# Low_Pass_Gate.net
KiCad netlist of a schematic drawn in EAGLE
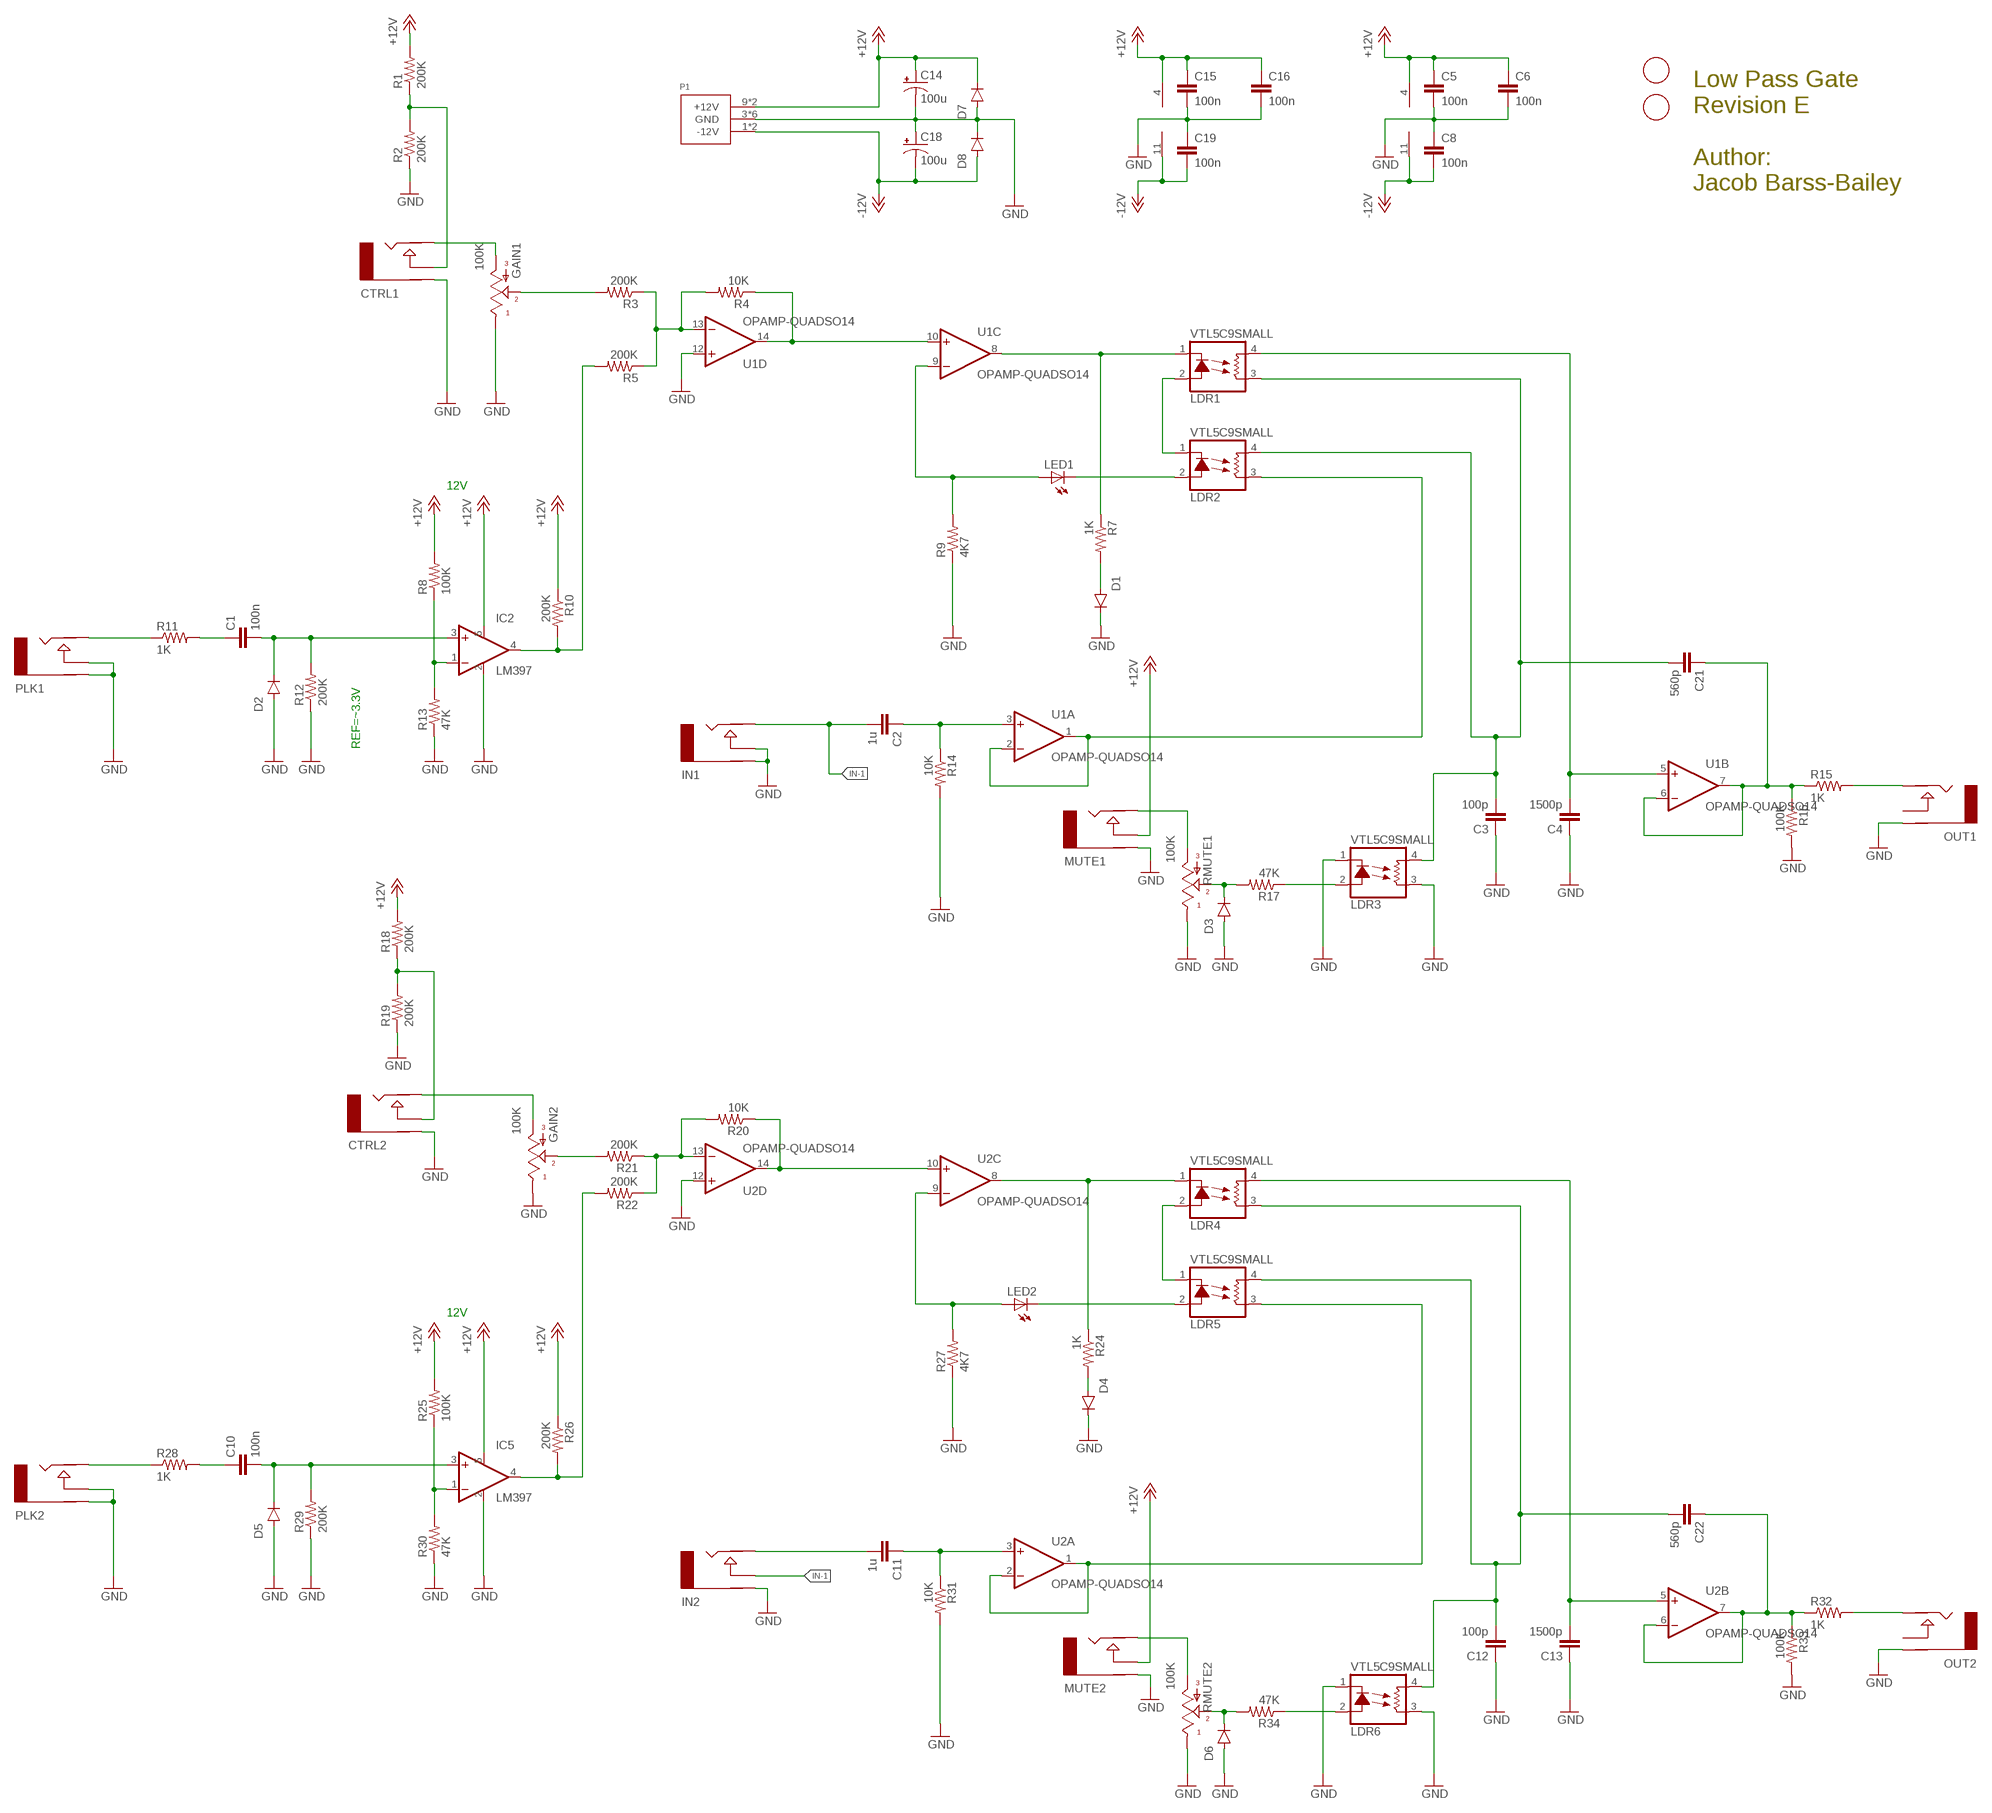
[diagram p0: schematic, sheet 1]

(export (version "E")
  (design (tool "Eeschema 10.0.6"))
  (components
    (comp (ref "C1")
      (value "100n")
      (footprint "eagle-import:0805")
      (libsource (lib "eagle-import") (part "CAP0805"))
    )
    (comp (ref "C2")
      (value "1u")
      (footprint "eagle-import:0805")
      (libsource (lib "eagle-import") (part "CAP0805"))
    )
    (comp (ref "C3")
      (value "100p")
      (footprint "eagle-import:0805")
      (libsource (lib "eagle-import") (part "CAP0805"))
    )
    (comp (ref "C4")
      (value "1500p")
      (footprint "eagle-import:0805")
      (libsource (lib "eagle-import") (part "CAP0805"))
    )
    (comp (ref "C5")
      (value "100n")
      (footprint "eagle-import:0805")
      (libsource (lib "eagle-import") (part "CAP0805"))
    )
    (comp (ref "C6")
      (value "100n")
      (footprint "eagle-import:0805")
      (libsource (lib "eagle-import") (part "CAP0805"))
    )
    (comp (ref "C8")
      (value "100n")
      (footprint "eagle-import:0805")
      (libsource (lib "eagle-import") (part "CAP0805"))
    )
    (comp (ref "C10")
      (value "100n")
      (footprint "eagle-import:0805")
      (libsource (lib "eagle-import") (part "CAP0805"))
    )
    (comp (ref "C11")
      (value "1u")
      (footprint "eagle-import:0805")
      (libsource (lib "eagle-import") (part "CAP0805"))
    )
    (comp (ref "C12")
      (value "100p")
      (footprint "eagle-import:0805")
      (libsource (lib "eagle-import") (part "CAP0805"))
    )
    (comp (ref "C13")
      (value "1500p")
      (footprint "eagle-import:0805")
      (libsource (lib "eagle-import") (part "CAP0805"))
    )
    (comp (ref "C14")
      (value "100u")
      (footprint "eagle-import:PANASONIC_D")
      (libsource (lib "eagle-import") (part "CAP_POLD"))
    )
    (comp (ref "C15")
      (value "100n")
      (footprint "eagle-import:0805")
      (libsource (lib "eagle-import") (part "CAP0805"))
    )
    (comp (ref "C16")
      (value "100n")
      (footprint "eagle-import:0805")
      (libsource (lib "eagle-import") (part "CAP0805"))
    )
    (comp (ref "C18")
      (value "100u")
      (footprint "eagle-import:PANASONIC_D")
      (libsource (lib "eagle-import") (part "CAP_POLD"))
    )
    (comp (ref "C19")
      (value "100n")
      (footprint "eagle-import:0805")
      (libsource (lib "eagle-import") (part "CAP0805"))
    )
    (comp (ref "C21")
      (value "560p")
      (footprint "eagle-import:0805")
      (libsource (lib "eagle-import") (part "CAP0805"))
    )
    (comp (ref "C22")
      (value "560p")
      (footprint "eagle-import:0805")
      (libsource (lib "eagle-import") (part "CAP0805"))
    )
    (comp (ref "CTRL1")
      (value "AUDIO-JACKINLINE-FLOATGND")
      (footprint "eagle-import:ERTHENVAR-JACK-INLINE-SHAREGND550")
      (libsource (lib "eagle-import") (part "AUDIO-JACKINLINE-FLOATGND"))
    )
    (comp (ref "CTRL2")
      (value "AUDIO-JACKINLINE-FLOATGND")
      (footprint "eagle-import:ERTHENVAR-JACK-INLINE-SHAREGND550")
      (libsource (lib "eagle-import") (part "AUDIO-JACKINLINE-FLOATGND"))
    )
    (comp (ref "D1")
      (value "DIODE-SOD323-W")
      (footprint "eagle-import:SOD323-W")
      (libsource (lib "eagle-import") (part "DIODE-SOD323-W"))
    )
    (comp (ref "D2")
      (value "DIODE-SOD323-W")
      (footprint "eagle-import:SOD323-W")
      (libsource (lib "eagle-import") (part "DIODE-SOD323-W"))
    )
    (comp (ref "D3")
      (value "DIODE-SOD323-W")
      (footprint "eagle-import:SOD323-W")
      (libsource (lib "eagle-import") (part "DIODE-SOD323-W"))
    )
    (comp (ref "D4")
      (value "DIODE-SOD323-W")
      (footprint "eagle-import:SOD323-W")
      (libsource (lib "eagle-import") (part "DIODE-SOD323-W"))
    )
    (comp (ref "D5")
      (value "DIODE-SOD323-W")
      (footprint "eagle-import:SOD323-W")
      (libsource (lib "eagle-import") (part "DIODE-SOD323-W"))
    )
    (comp (ref "D6")
      (value "DIODE-SOD323-W")
      (footprint "eagle-import:SOD323-W")
      (libsource (lib "eagle-import") (part "DIODE-SOD323-W"))
    )
    (comp (ref "D7")
      (value "DIODE-SOD323-W")
      (footprint "eagle-import:SOD323-W")
      (libsource (lib "eagle-import") (part "DIODE-SOD323-W"))
    )
    (comp (ref "D8")
      (value "DIODE-SOD323-W")
      (footprint "eagle-import:SOD323-W")
      (libsource (lib "eagle-import") (part "DIODE-SOD323-W"))
    )
    (comp (ref "GAIN1")
      (value "100K")
      (footprint "eagle-import:ALPS_POT_KIT")
      (libsource (lib "eagle-import") (part "POTALPS-KIT"))
    )
    (comp (ref "GAIN2")
      (value "100K")
      (footprint "eagle-import:ALPS_POT_KIT")
      (libsource (lib "eagle-import") (part "POTALPS-KIT"))
    )
    (comp (ref "IC2")
      (value "LM397")
      (footprint "eagle-import:SOT23-5")
      (libsource (lib "eagle-import") (part "LM397"))
    )
    (comp (ref "IC5")
      (value "LM397")
      (footprint "eagle-import:SOT23-5")
      (libsource (lib "eagle-import") (part "LM397"))
    )
    (comp (ref "IN1")
      (value "AUDIO-JACKINLINE-FLOATGND")
      (footprint "eagle-import:ERTHENVAR-JACK-INLINE-SHAREGND550")
      (libsource (lib "eagle-import") (part "AUDIO-JACKINLINE-FLOATGND"))
    )
    (comp (ref "IN2")
      (value "AUDIO-JACKINLINE-FLOATGND")
      (footprint "eagle-import:ERTHENVAR-JACK-INLINE-SHAREGND550")
      (libsource (lib "eagle-import") (part "AUDIO-JACKINLINE-FLOATGND"))
    )
    (comp (ref "LDR1")
      (value "VTL5C9SMALL")
      (footprint "eagle-import:VTL5C-SMALL")
      (fields (field (name "MF") "VACTEC PHOTO") (field (name "MPN") "VTL5C9"))
      (libsource (lib "eagle-import") (part "VTL5CSMALL9"))
    )
    (comp (ref "LDR2")
      (value "VTL5C9SMALL")
      (footprint "eagle-import:VTL5C-SMALL")
      (fields (field (name "MF") "VACTEC PHOTO") (field (name "MPN") "VTL5C9"))
      (libsource (lib "eagle-import") (part "VTL5CSMALL9"))
    )
    (comp (ref "LDR3")
      (value "VTL5C9SMALL")
      (footprint "eagle-import:VTL5C-SMALL")
      (fields (field (name "MF") "VACTEC PHOTO") (field (name "MPN") "VTL5C9"))
      (libsource (lib "eagle-import") (part "VTL5CSMALL9"))
    )
    (comp (ref "LDR4")
      (value "VTL5C9SMALL")
      (footprint "eagle-import:VTL5C-SMALL")
      (fields (field (name "MF") "VACTEC PHOTO") (field (name "MPN") "VTL5C9"))
      (libsource (lib "eagle-import") (part "VTL5CSMALL9"))
    )
    (comp (ref "LDR5")
      (value "VTL5C9SMALL")
      (footprint "eagle-import:VTL5C-SMALL")
      (fields (field (name "MF") "VACTEC PHOTO") (field (name "MPN") "VTL5C9"))
      (libsource (lib "eagle-import") (part "VTL5CSMALL9"))
    )
    (comp (ref "LDR6")
      (value "VTL5C9SMALL")
      (footprint "eagle-import:VTL5C-SMALL")
      (fields (field (name "MF") "VACTEC PHOTO") (field (name "MPN") "VTL5C9"))
      (libsource (lib "eagle-import") (part "VTL5CSMALL9"))
    )
    (comp (ref "LED1")
      (value "LED3MM")
      (footprint "eagle-import:LED3MM")
      (libsource (lib "eagle-import") (part "LED3MM"))
    )
    (comp (ref "LED2")
      (value "LED3MM")
      (footprint "eagle-import:LED3MM")
      (libsource (lib "eagle-import") (part "LED3MM"))
    )
    (comp (ref "MUTE1")
      (value "AUDIO-JACKINLINE")
      (footprint "eagle-import:ERTHENVAR-JACK-INLINE")
      (libsource (lib "eagle-import") (part "AUDIO-JACKINLINE"))
    )
    (comp (ref "MUTE2")
      (value "AUDIO-JACKINLINE")
      (footprint "eagle-import:ERTHENVAR-JACK-INLINE")
      (libsource (lib "eagle-import") (part "AUDIO-JACKINLINE"))
    )
    (comp (ref "OUT1")
      (value "AUDIO-JACKINLINE")
      (footprint "eagle-import:ERTHENVAR-JACK-INLINE")
      (libsource (lib "eagle-import") (part "AUDIO-JACKINLINE"))
    )
    (comp (ref "OUT2")
      (value "AUDIO-JACKINLINE")
      (footprint "eagle-import:ERTHENVAR-JACK-INLINE")
      (libsource (lib "eagle-import") (part "AUDIO-JACKINLINE"))
    )
    (comp (ref "P1")
      (value "POWER_SIMPLE10_SHROUDED")
      (footprint "eagle-import:POWER_10_SHROUDED")
      (libsource (lib "eagle-import") (part "POWER_SIMPLE10_SHROUDED"))
    )
    (comp (ref "PLK1")
      (value "AUDIO-JACKINLINE")
      (footprint "eagle-import:ERTHENVAR-JACK-INLINE")
      (libsource (lib "eagle-import") (part "AUDIO-JACKINLINE"))
    )
    (comp (ref "PLK2")
      (value "AUDIO-JACKINLINE")
      (footprint "eagle-import:ERTHENVAR-JACK-INLINE")
      (libsource (lib "eagle-import") (part "AUDIO-JACKINLINE"))
    )
    (comp (ref "R1")
      (value "200K")
      (footprint "eagle-import:0603-RES")
      (libsource (lib "eagle-import") (part "RESISTOR0603-RES"))
    )
    (comp (ref "R2")
      (value "200K")
      (footprint "eagle-import:0603-RES")
      (libsource (lib "eagle-import") (part "RESISTOR0603-RES"))
    )
    (comp (ref "R3")
      (value "200K")
      (footprint "eagle-import:0603-RES")
      (libsource (lib "eagle-import") (part "RESISTOR0603-RES"))
    )
    (comp (ref "R4")
      (value "10K")
      (footprint "eagle-import:0603-RES")
      (libsource (lib "eagle-import") (part "RESISTOR0603-RES"))
    )
    (comp (ref "R5")
      (value "200K")
      (footprint "eagle-import:0603-RES")
      (libsource (lib "eagle-import") (part "RESISTOR0603-RES"))
    )
    (comp (ref "R7")
      (value "1K")
      (footprint "eagle-import:0603-RES")
      (libsource (lib "eagle-import") (part "RESISTOR0603-RES"))
    )
    (comp (ref "R8")
      (value "100K")
      (footprint "eagle-import:0603-RES")
      (libsource (lib "eagle-import") (part "RESISTOR0603-RES"))
    )
    (comp (ref "R9")
      (value "4K7")
      (footprint "eagle-import:0603-RES")
      (libsource (lib "eagle-import") (part "RESISTOR0603-RES"))
    )
    (comp (ref "R10")
      (value "200K")
      (footprint "eagle-import:0603-RES")
      (libsource (lib "eagle-import") (part "RESISTOR0603-RES"))
    )
    (comp (ref "R11")
      (value "1K")
      (footprint "eagle-import:0603-RES")
      (libsource (lib "eagle-import") (part "RESISTOR0603-RES"))
    )
    (comp (ref "R12")
      (value "200K")
      (footprint "eagle-import:0603-RES")
      (libsource (lib "eagle-import") (part "RESISTOR0603-RES"))
    )
    (comp (ref "R13")
      (value "47K")
      (footprint "eagle-import:0603-RES")
      (libsource (lib "eagle-import") (part "RESISTOR0603-RES"))
    )
    (comp (ref "R14")
      (value "10K")
      (footprint "eagle-import:0603-RES")
      (libsource (lib "eagle-import") (part "RESISTOR0603-RES"))
    )
    (comp (ref "R15")
      (value "1K")
      (footprint "eagle-import:0603-RES")
      (libsource (lib "eagle-import") (part "RESISTOR0603-RES"))
    )
    (comp (ref "R16")
      (value "100K")
      (footprint "eagle-import:0603-RES")
      (libsource (lib "eagle-import") (part "RESISTOR0603-RES"))
    )
    (comp (ref "R17")
      (value "47K")
      (footprint "eagle-import:0603-RES")
      (libsource (lib "eagle-import") (part "RESISTOR0603-RES"))
    )
    (comp (ref "R18")
      (value "200K")
      (footprint "eagle-import:0603-RES")
      (libsource (lib "eagle-import") (part "RESISTOR0603-RES"))
    )
    (comp (ref "R19")
      (value "200K")
      (footprint "eagle-import:0603-RES")
      (libsource (lib "eagle-import") (part "RESISTOR0603-RES"))
    )
    (comp (ref "R20")
      (value "10K")
      (footprint "eagle-import:0603-RES")
      (libsource (lib "eagle-import") (part "RESISTOR0603-RES"))
    )
    (comp (ref "R21")
      (value "200K")
      (footprint "eagle-import:0603-RES")
      (libsource (lib "eagle-import") (part "RESISTOR0603-RES"))
    )
    (comp (ref "R22")
      (value "200K")
      (footprint "eagle-import:0603-RES")
      (libsource (lib "eagle-import") (part "RESISTOR0603-RES"))
    )
    (comp (ref "R24")
      (value "1K")
      (footprint "eagle-import:0603-RES")
      (libsource (lib "eagle-import") (part "RESISTOR0603-RES"))
    )
    (comp (ref "R25")
      (value "100K")
      (footprint "eagle-import:0603-RES")
      (libsource (lib "eagle-import") (part "RESISTOR0603-RES"))
    )
    (comp (ref "R26")
      (value "200K")
      (footprint "eagle-import:0603-RES")
      (libsource (lib "eagle-import") (part "RESISTOR0603-RES"))
    )
    (comp (ref "R27")
      (value "4K7")
      (footprint "eagle-import:0603-RES")
      (libsource (lib "eagle-import") (part "RESISTOR0603-RES"))
    )
    (comp (ref "R28")
      (value "1K")
      (footprint "eagle-import:0603-RES")
      (libsource (lib "eagle-import") (part "RESISTOR0603-RES"))
    )
    (comp (ref "R29")
      (value "200K")
      (footprint "eagle-import:0603-RES")
      (libsource (lib "eagle-import") (part "RESISTOR0603-RES"))
    )
    (comp (ref "R30")
      (value "47K")
      (footprint "eagle-import:0603-RES")
      (libsource (lib "eagle-import") (part "RESISTOR0603-RES"))
    )
    (comp (ref "R31")
      (value "10K")
      (footprint "eagle-import:0603-RES")
      (libsource (lib "eagle-import") (part "RESISTOR0603-RES"))
    )
    (comp (ref "R32")
      (value "1K")
      (footprint "eagle-import:0603-RES")
      (libsource (lib "eagle-import") (part "RESISTOR0603-RES"))
    )
    (comp (ref "R33")
      (value "100K")
      (footprint "eagle-import:0603-RES")
      (libsource (lib "eagle-import") (part "RESISTOR0603-RES"))
    )
    (comp (ref "R34")
      (value "47K")
      (footprint "eagle-import:0603-RES")
      (libsource (lib "eagle-import") (part "RESISTOR0603-RES"))
    )
    (comp (ref "RMUTE1")
      (value "100K")
      (footprint "eagle-import:ALPS_POT_KIT")
      (libsource (lib "eagle-import") (part "POTALPS-KIT"))
    )
    (comp (ref "RMUTE2")
      (value "100K")
      (footprint "eagle-import:ALPS_POT_KIT")
      (libsource (lib "eagle-import") (part "POTALPS-KIT"))
    )
    (comp (ref "U$1")
      (value "FIDUCIAL")
      (footprint "eagle-import:FIDUCIAL_1MM")
      (libsource (lib "eagle-import") (part "FIDUCIAL"))
    )
    (comp (ref "U$2")
      (value "FIDUCIAL")
      (footprint "eagle-import:FIDUCIAL_1MM")
      (libsource (lib "eagle-import") (part "FIDUCIAL"))
    )
    (comp (ref "U1")
      (value "OPAMP-QUADSO14")
      (footprint "eagle-import:SO14")
      (libsource (lib "eagle-import") (part "OPAMP-QUADSO14"))
    )
    (comp (ref "U2")
      (value "OPAMP-QUADSO14")
      (footprint "eagle-import:SO14")
      (libsource (lib "eagle-import") (part "OPAMP-QUADSO14"))
    )
  )
  (nets
    (net (code "1") (name "+12V") (class "Default")
      (node (ref "C14") (pin "+") (pinfunction "+_+") (pintype "passive"))
      (node (ref "C15") (pin "1") (pinfunction "1_1") (pintype "passive"))
      (node (ref "C16") (pin "1") (pinfunction "1_1") (pintype "passive"))
      (node (ref "C5") (pin "1") (pinfunction "1_1") (pintype "passive"))
      (node (ref "C6") (pin "1") (pinfunction "1_1") (pintype "passive"))
      (node (ref "D7") (pin "C") (pinfunction "C_C") (pintype "passive"))
      (node (ref "IC2") (pin "5") (pinfunction "V+_5") (pintype "power_in"))
      (node (ref "IC5") (pin "5") (pinfunction "V+_5") (pintype "power_in"))
      (node (ref "MUTE1") (pin "N") (pinfunction "NORM_N") (pintype "bidirectional"))
      (node (ref "MUTE2") (pin "N") (pinfunction "NORM_N") (pintype "bidirectional"))
      (node (ref "P1") (pin "10") (pinfunction "+12V_10") (pintype "bidirectional"))
      (node (ref "P1") (pin "9") (pinfunction "+12V_9") (pintype "bidirectional"))
      (node (ref "R1") (pin "2") (pinfunction "2_2") (pintype "passive"))
      (node (ref "R10") (pin "1") (pinfunction "1_1") (pintype "passive"))
      (node (ref "R18") (pin "2") (pinfunction "2_2") (pintype "passive"))
      (node (ref "R25") (pin "2") (pinfunction "2_2") (pintype "passive"))
      (node (ref "R26") (pin "1") (pinfunction "1_1") (pintype "passive"))
      (node (ref "R8") (pin "2") (pinfunction "2_2") (pintype "passive"))
      (node (ref "U1") (pin "4") (pinfunction "VCC_4") (pintype "power_in"))
      (node (ref "U2") (pin "4") (pinfunction "VCC_4") (pintype "power_in"))
    )
    (net (code "2") (name "-12V") (class "Default")
      (node (ref "C18") (pin "-") (pinfunction "-_-") (pintype "passive"))
      (node (ref "C19") (pin "2") (pinfunction "2_2") (pintype "passive"))
      (node (ref "C8") (pin "2") (pinfunction "2_2") (pintype "passive"))
      (node (ref "D8") (pin "A") (pinfunction "A_A") (pintype "passive"))
      (node (ref "P1") (pin "1") (pinfunction "-12V_1") (pintype "bidirectional"))
      (node (ref "P1") (pin "2") (pinfunction "-12V_2") (pintype "bidirectional"))
      (node (ref "U1") (pin "11") (pinfunction "VEE_11") (pintype "power_in"))
      (node (ref "U2") (pin "11") (pinfunction "VEE_11") (pintype "power_in"))
    )
    (net (code "3") (name "GND") (class "Default")
      (node (ref "C12") (pin "1") (pinfunction "1_1") (pintype "passive"))
      (node (ref "C13") (pin "1") (pinfunction "1_1") (pintype "passive"))
      (node (ref "C14") (pin "-") (pinfunction "-_-") (pintype "passive"))
      (node (ref "C15") (pin "2") (pinfunction "2_2") (pintype "passive"))
      (node (ref "C16") (pin "2") (pinfunction "2_2") (pintype "passive"))
      (node (ref "C18") (pin "+") (pinfunction "+_+") (pintype "passive"))
      (node (ref "C19") (pin "1") (pinfunction "1_1") (pintype "passive"))
      (node (ref "C3") (pin "1") (pinfunction "1_1") (pintype "passive"))
      (node (ref "C4") (pin "1") (pinfunction "1_1") (pintype "passive"))
      (node (ref "C5") (pin "2") (pinfunction "2_2") (pintype "passive"))
      (node (ref "C6") (pin "2") (pinfunction "2_2") (pintype "passive"))
      (node (ref "C8") (pin "1") (pinfunction "1_1") (pintype "passive"))
      (node (ref "CTRL1") (pin "G") (pinfunction "RING_G") (pintype "bidirectional"))
      (node (ref "CTRL2") (pin "G") (pinfunction "RING_G") (pintype "bidirectional"))
      (node (ref "D1") (pin "C") (pinfunction "C_C") (pintype "passive"))
      (node (ref "D2") (pin "A") (pinfunction "A_A") (pintype "passive"))
      (node (ref "D3") (pin "A") (pinfunction "A_A") (pintype "passive"))
      (node (ref "D4") (pin "C") (pinfunction "C_C") (pintype "passive"))
      (node (ref "D5") (pin "A") (pinfunction "A_A") (pintype "passive"))
      (node (ref "D6") (pin "A") (pinfunction "A_A") (pintype "passive"))
      (node (ref "D7") (pin "A") (pinfunction "A_A") (pintype "passive"))
      (node (ref "D8") (pin "C") (pinfunction "C_C") (pintype "passive"))
      (node (ref "GAIN1") (pin "P$1") (pinfunction "E_P$1") (pintype "passive"))
      (node (ref "GAIN2") (pin "P$1") (pinfunction "E_P$1") (pintype "passive"))
      (node (ref "IC2") (pin "2") (pinfunction "GND_2") (pintype "power_in"))
      (node (ref "IC5") (pin "2") (pinfunction "GND_2") (pintype "power_in"))
      (node (ref "IN1") (pin "G") (pinfunction "RING_G") (pintype "bidirectional"))
      (node (ref "IN1") (pin "N") (pinfunction "NORM_N") (pintype "bidirectional"))
      (node (ref "IN2") (pin "G") (pinfunction "RING_G") (pintype "bidirectional"))
      (node (ref "LDR3") (pin "1") (pinfunction "C_1") (pintype "passive"))
      (node (ref "LDR3") (pin "3") (pinfunction "L1_3") (pintype "passive"))
      (node (ref "LDR6") (pin "1") (pinfunction "C_1") (pintype "passive"))
      (node (ref "LDR6") (pin "3") (pinfunction "L1_3") (pintype "passive"))
      (node (ref "MUTE1") (pin "G") (pinfunction "RING_G") (pintype "bidirectional"))
      (node (ref "MUTE2") (pin "G") (pinfunction "RING_G") (pintype "bidirectional"))
      (node (ref "OUT1") (pin "G") (pinfunction "RING_G") (pintype "bidirectional"))
      (node (ref "OUT2") (pin "G") (pinfunction "RING_G") (pintype "bidirectional"))
      (node (ref "P1") (pin "3") (pinfunction "GND_3") (pintype "bidirectional"))
      (node (ref "P1") (pin "4") (pinfunction "GND_4") (pintype "bidirectional"))
      (node (ref "P1") (pin "5") (pinfunction "GND_5") (pintype "bidirectional"))
      (node (ref "P1") (pin "6") (pinfunction "GND_6") (pintype "bidirectional"))
      (node (ref "P1") (pin "7") (pinfunction "GND_7") (pintype "bidirectional"))
      (node (ref "P1") (pin "8") (pinfunction "GND_8") (pintype "bidirectional"))
      (node (ref "PLK1") (pin "G") (pinfunction "RING_G") (pintype "bidirectional"))
      (node (ref "PLK1") (pin "N") (pinfunction "NORM_N") (pintype "bidirectional"))
      (node (ref "PLK2") (pin "G") (pinfunction "RING_G") (pintype "bidirectional"))
      (node (ref "PLK2") (pin "N") (pinfunction "NORM_N") (pintype "bidirectional"))
      (node (ref "R12") (pin "1") (pinfunction "1_1") (pintype "passive"))
      (node (ref "R13") (pin "1") (pinfunction "1_1") (pintype "passive"))
      (node (ref "R14") (pin "2") (pinfunction "2_2") (pintype "passive"))
      (node (ref "R16") (pin "2") (pinfunction "2_2") (pintype "passive"))
      (node (ref "R19") (pin "1") (pinfunction "1_1") (pintype "passive"))
      (node (ref "R2") (pin "1") (pinfunction "1_1") (pintype "passive"))
      (node (ref "R27") (pin "1") (pinfunction "1_1") (pintype "passive"))
      (node (ref "R29") (pin "1") (pinfunction "1_1") (pintype "passive"))
      (node (ref "R30") (pin "1") (pinfunction "1_1") (pintype "passive"))
      (node (ref "R31") (pin "2") (pinfunction "2_2") (pintype "passive"))
      (node (ref "R33") (pin "2") (pinfunction "2_2") (pintype "passive"))
      (node (ref "R9") (pin "1") (pinfunction "1_1") (pintype "passive"))
      (node (ref "RMUTE1") (pin "P$1") (pinfunction "E_P$1") (pintype "passive"))
      (node (ref "RMUTE2") (pin "P$1") (pinfunction "E_P$1") (pintype "passive"))
      (node (ref "U1") (pin "12") (pinfunction "+IN_12") (pintype "input"))
      (node (ref "U2") (pin "12") (pinfunction "+IN_12") (pintype "input"))
    )
    (net (code "4") (name "IN-1") (class "Default")
      (node (ref "C2") (pin "2") (pinfunction "2_2") (pintype "passive"))
      (node (ref "IN1") (pin "T") (pinfunction "TIP_T") (pintype "bidirectional"))
      (node (ref "IN2") (pin "N") (pinfunction "NORM_N") (pintype "bidirectional"))
    )
    (net (code "5") (name "Net-(C1-Pad1)") (class "Default")
      (node (ref "C1") (pin "1") (pinfunction "1_1") (pintype "passive"))
      (node (ref "R11") (pin "2") (pinfunction "2_2") (pintype "passive"))
    )
    (net (code "6") (name "Net-(C10-Pad1)") (class "Default")
      (node (ref "C10") (pin "1") (pinfunction "1_1") (pintype "passive"))
      (node (ref "R28") (pin "2") (pinfunction "2_2") (pintype "passive"))
    )
    (net (code "7") (name "Net-(CTRL1-NORM)") (class "Default")
      (node (ref "CTRL1") (pin "N") (pinfunction "NORM_N") (pintype "bidirectional"))
      (node (ref "R1") (pin "1") (pinfunction "1_1") (pintype "passive"))
      (node (ref "R2") (pin "2") (pinfunction "2_2") (pintype "passive"))
    )
    (net (code "8") (name "Net-(CTRL1-TIP)") (class "Default")
      (node (ref "CTRL1") (pin "T") (pinfunction "TIP_T") (pintype "bidirectional"))
      (node (ref "GAIN1") (pin "P$3") (pinfunction "A_P$3") (pintype "passive"))
    )
    (net (code "9") (name "Net-(CTRL2-NORM)") (class "Default")
      (node (ref "CTRL2") (pin "N") (pinfunction "NORM_N") (pintype "bidirectional"))
      (node (ref "R18") (pin "1") (pinfunction "1_1") (pintype "passive"))
      (node (ref "R19") (pin "2") (pinfunction "2_2") (pintype "passive"))
    )
    (net (code "10") (name "Net-(CTRL2-TIP)") (class "Default")
      (node (ref "CTRL2") (pin "T") (pinfunction "TIP_T") (pintype "bidirectional"))
      (node (ref "GAIN2") (pin "P$3") (pinfunction "A_P$3") (pintype "passive"))
    )
    (net (code "11") (name "Net-(D1-PadA)") (class "Default")
      (node (ref "D1") (pin "A") (pinfunction "A_A") (pintype "passive"))
      (node (ref "R7") (pin "2") (pinfunction "2_2") (pintype "passive"))
    )
    (net (code "12") (name "Net-(D4-PadA)") (class "Default")
      (node (ref "D4") (pin "A") (pinfunction "A_A") (pintype "passive"))
      (node (ref "R24") (pin "2") (pinfunction "2_2") (pintype "passive"))
    )
    (net (code "13") (name "Net-(GAIN1-S)") (class "Default")
      (node (ref "GAIN1") (pin "P$2") (pinfunction "S_P$2") (pintype "passive"))
      (node (ref "R3") (pin "2") (pinfunction "2_2") (pintype "passive"))
    )
    (net (code "14") (name "Net-(GAIN2-S)") (class "Default")
      (node (ref "GAIN2") (pin "P$2") (pinfunction "S_P$2") (pintype "passive"))
      (node (ref "R21") (pin "2") (pinfunction "2_2") (pintype "passive"))
    )
    (net (code "15") (name "Net-(IC2-+IN)") (class "Default")
      (node (ref "C1") (pin "2") (pinfunction "2_2") (pintype "passive"))
      (node (ref "D2") (pin "C") (pinfunction "C_C") (pintype "passive"))
      (node (ref "IC2") (pin "3") (pinfunction "+IN_3") (pintype "input"))
      (node (ref "R12") (pin "2") (pinfunction "2_2") (pintype "passive"))
    )
    (net (code "16") (name "Net-(IC2--IN)") (class "Default")
      (node (ref "IC2") (pin "1") (pinfunction "-IN_1") (pintype "input"))
      (node (ref "R13") (pin "2") (pinfunction "2_2") (pintype "passive"))
      (node (ref "R8") (pin "1") (pinfunction "1_1") (pintype "passive"))
    )
    (net (code "17") (name "Net-(IC2-OUT)") (class "Default")
      (node (ref "IC2") (pin "4") (pinfunction "OUT_4") (pintype "output"))
      (node (ref "R10") (pin "2") (pinfunction "2_2") (pintype "passive"))
      (node (ref "R5") (pin "2") (pinfunction "2_2") (pintype "passive"))
    )
    (net (code "18") (name "Net-(IC5-+IN)") (class "Default")
      (node (ref "C10") (pin "2") (pinfunction "2_2") (pintype "passive"))
      (node (ref "D5") (pin "C") (pinfunction "C_C") (pintype "passive"))
      (node (ref "IC5") (pin "3") (pinfunction "+IN_3") (pintype "input"))
      (node (ref "R29") (pin "2") (pinfunction "2_2") (pintype "passive"))
    )
    (net (code "19") (name "Net-(IC5--IN)") (class "Default")
      (node (ref "IC5") (pin "1") (pinfunction "-IN_1") (pintype "input"))
      (node (ref "R25") (pin "1") (pinfunction "1_1") (pintype "passive"))
      (node (ref "R30") (pin "2") (pinfunction "2_2") (pintype "passive"))
    )
    (net (code "20") (name "Net-(IC5-OUT)") (class "Default")
      (node (ref "IC5") (pin "4") (pinfunction "OUT_4") (pintype "output"))
      (node (ref "R22") (pin "2") (pinfunction "2_2") (pintype "passive"))
      (node (ref "R26") (pin "2") (pinfunction "2_2") (pintype "passive"))
    )
    (net (code "21") (name "Net-(IN2-TIP)") (class "Default")
      (node (ref "C11") (pin "2") (pinfunction "2_2") (pintype "passive"))
      (node (ref "IN2") (pin "T") (pinfunction "TIP_T") (pintype "bidirectional"))
    )
    (net (code "22") (name "Net-(LDR1-A)") (class "Default")
      (node (ref "LDR1") (pin "2") (pinfunction "A_2") (pintype "passive"))
      (node (ref "LDR2") (pin "1") (pinfunction "C_1") (pintype "passive"))
    )
    (net (code "23") (name "Net-(LDR1-C)") (class "Default")
      (node (ref "LDR1") (pin "1") (pinfunction "C_1") (pintype "passive"))
      (node (ref "R7") (pin "1") (pinfunction "1_1") (pintype "passive"))
      (node (ref "U1") (pin "8") (pinfunction "OUT_8") (pintype "output"))
    )
    (net (code "24") (name "Net-(LDR1-L1)") (class "Default")
      (node (ref "C21") (pin "2") (pinfunction "2_2") (pintype "passive"))
      (node (ref "C3") (pin "2") (pinfunction "2_2") (pintype "passive"))
      (node (ref "LDR1") (pin "3") (pinfunction "L1_3") (pintype "passive"))
      (node (ref "LDR2") (pin "4") (pinfunction "L2_4") (pintype "passive"))
      (node (ref "LDR3") (pin "4") (pinfunction "L2_4") (pintype "passive"))
    )
    (net (code "25") (name "Net-(LDR1-L2)") (class "Default")
      (node (ref "C4") (pin "2") (pinfunction "2_2") (pintype "passive"))
      (node (ref "LDR1") (pin "4") (pinfunction "L2_4") (pintype "passive"))
      (node (ref "U1") (pin "5") (pinfunction "+IN_5") (pintype "input"))
    )
    (net (code "26") (name "Net-(LDR2-A)") (class "Default")
      (node (ref "LDR2") (pin "2") (pinfunction "A_2") (pintype "passive"))
      (node (ref "LED1") (pin "K") (pinfunction "C_K") (pintype "passive"))
    )
    (net (code "27") (name "Net-(LDR2-L1)") (class "Default")
      (node (ref "LDR2") (pin "3") (pinfunction "L1_3") (pintype "passive"))
      (node (ref "U1") (pin "1") (pinfunction "OUT_1") (pintype "output"))
      (node (ref "U1") (pin "2") (pinfunction "-IN_2") (pintype "input"))
    )
    (net (code "28") (name "Net-(LDR3-A)") (class "Default")
      (node (ref "LDR3") (pin "2") (pinfunction "A_2") (pintype "passive"))
      (node (ref "R17") (pin "1") (pinfunction "1_1") (pintype "passive"))
    )
    (net (code "29") (name "Net-(LDR4-A)") (class "Default")
      (node (ref "LDR4") (pin "2") (pinfunction "A_2") (pintype "passive"))
      (node (ref "LDR5") (pin "1") (pinfunction "C_1") (pintype "passive"))
    )
    (net (code "30") (name "Net-(LDR4-C)") (class "Default")
      (node (ref "LDR4") (pin "1") (pinfunction "C_1") (pintype "passive"))
      (node (ref "R24") (pin "1") (pinfunction "1_1") (pintype "passive"))
      (node (ref "U2") (pin "8") (pinfunction "OUT_8") (pintype "output"))
    )
    (net (code "31") (name "Net-(LDR4-L1)") (class "Default")
      (node (ref "C12") (pin "2") (pinfunction "2_2") (pintype "passive"))
      (node (ref "C22") (pin "2") (pinfunction "2_2") (pintype "passive"))
      (node (ref "LDR4") (pin "3") (pinfunction "L1_3") (pintype "passive"))
      (node (ref "LDR5") (pin "4") (pinfunction "L2_4") (pintype "passive"))
      (node (ref "LDR6") (pin "4") (pinfunction "L2_4") (pintype "passive"))
    )
    (net (code "32") (name "Net-(LDR4-L2)") (class "Default")
      (node (ref "C13") (pin "2") (pinfunction "2_2") (pintype "passive"))
      (node (ref "LDR4") (pin "4") (pinfunction "L2_4") (pintype "passive"))
      (node (ref "U2") (pin "5") (pinfunction "+IN_5") (pintype "input"))
    )
    (net (code "33") (name "Net-(LDR5-A)") (class "Default")
      (node (ref "LDR5") (pin "2") (pinfunction "A_2") (pintype "passive"))
      (node (ref "LED2") (pin "K") (pinfunction "C_K") (pintype "passive"))
    )
    (net (code "34") (name "Net-(LDR5-L1)") (class "Default")
      (node (ref "LDR5") (pin "3") (pinfunction "L1_3") (pintype "passive"))
      (node (ref "U2") (pin "1") (pinfunction "OUT_1") (pintype "output"))
      (node (ref "U2") (pin "2") (pinfunction "-IN_2") (pintype "input"))
    )
    (net (code "35") (name "Net-(LDR6-A)") (class "Default")
      (node (ref "LDR6") (pin "2") (pinfunction "A_2") (pintype "passive"))
      (node (ref "R34") (pin "1") (pinfunction "1_1") (pintype "passive"))
    )
    (net (code "36") (name "Net-(MUTE1-TIP)") (class "Default")
      (node (ref "MUTE1") (pin "T") (pinfunction "TIP_T") (pintype "bidirectional"))
      (node (ref "RMUTE1") (pin "P$3") (pinfunction "A_P$3") (pintype "passive"))
    )
    (net (code "37") (name "Net-(MUTE2-TIP)") (class "Default")
      (node (ref "MUTE2") (pin "T") (pinfunction "TIP_T") (pintype "bidirectional"))
      (node (ref "RMUTE2") (pin "P$3") (pinfunction "A_P$3") (pintype "passive"))
    )
    (net (code "38") (name "Net-(OUT1-TIP)") (class "Default")
      (node (ref "OUT1") (pin "T") (pinfunction "TIP_T") (pintype "bidirectional"))
      (node (ref "R15") (pin "2") (pinfunction "2_2") (pintype "passive"))
    )
    (net (code "39") (name "Net-(OUT2-TIP)") (class "Default")
      (node (ref "OUT2") (pin "T") (pinfunction "TIP_T") (pintype "bidirectional"))
      (node (ref "R32") (pin "2") (pinfunction "2_2") (pintype "passive"))
    )
    (net (code "40") (name "Net-(PLK1-TIP)") (class "Default")
      (node (ref "PLK1") (pin "T") (pinfunction "TIP_T") (pintype "bidirectional"))
      (node (ref "R11") (pin "1") (pinfunction "1_1") (pintype "passive"))
    )
    (net (code "41") (name "Net-(PLK2-TIP)") (class "Default")
      (node (ref "PLK2") (pin "T") (pinfunction "TIP_T") (pintype "bidirectional"))
      (node (ref "R28") (pin "1") (pinfunction "1_1") (pintype "passive"))
    )
    (net (code "42") (name "Net-(RMUTE1-S)") (class "Default")
      (node (ref "D3") (pin "C") (pinfunction "C_C") (pintype "passive"))
      (node (ref "R17") (pin "2") (pinfunction "2_2") (pintype "passive"))
      (node (ref "RMUTE1") (pin "P$2") (pinfunction "S_P$2") (pintype "passive"))
    )
    (net (code "43") (name "Net-(RMUTE2-S)") (class "Default")
      (node (ref "D6") (pin "C") (pinfunction "C_C") (pintype "passive"))
      (node (ref "R34") (pin "2") (pinfunction "2_2") (pintype "passive"))
      (node (ref "RMUTE2") (pin "P$2") (pinfunction "S_P$2") (pintype "passive"))
    )
    (net (code "44") (name "Net-(U1A-+IN)") (class "Default")
      (node (ref "C2") (pin "1") (pinfunction "1_1") (pintype "passive"))
      (node (ref "R14") (pin "1") (pinfunction "1_1") (pintype "passive"))
      (node (ref "U1") (pin "3") (pinfunction "+IN_3") (pintype "input"))
    )
    (net (code "45") (name "Net-(U1B--IN)") (class "Default")
      (node (ref "C21") (pin "1") (pinfunction "1_1") (pintype "passive"))
      (node (ref "R15") (pin "1") (pinfunction "1_1") (pintype "passive"))
      (node (ref "R16") (pin "1") (pinfunction "1_1") (pintype "passive"))
      (node (ref "U1") (pin "6") (pinfunction "-IN_6") (pintype "input"))
      (node (ref "U1") (pin "7") (pinfunction "OUT_7") (pintype "output"))
    )
    (net (code "46") (name "Net-(U1C-+IN)") (class "Default")
      (node (ref "R4") (pin "1") (pinfunction "1_1") (pintype "passive"))
      (node (ref "U1") (pin "10") (pinfunction "+IN_10") (pintype "input"))
      (node (ref "U1") (pin "14") (pinfunction "OUT_14") (pintype "output"))
    )
    (net (code "47") (name "Net-(U1C--IN)") (class "Default")
      (node (ref "LED1") (pin "A") (pinfunction "A_A") (pintype "passive"))
      (node (ref "R9") (pin "2") (pinfunction "2_2") (pintype "passive"))
      (node (ref "U1") (pin "9") (pinfunction "-IN_9") (pintype "input"))
    )
    (net (code "48") (name "Net-(U1D--IN)") (class "Default")
      (node (ref "R3") (pin "1") (pinfunction "1_1") (pintype "passive"))
      (node (ref "R4") (pin "2") (pinfunction "2_2") (pintype "passive"))
      (node (ref "R5") (pin "1") (pinfunction "1_1") (pintype "passive"))
      (node (ref "U1") (pin "13") (pinfunction "-IN_13") (pintype "input"))
    )
    (net (code "49") (name "Net-(U2A-+IN)") (class "Default")
      (node (ref "C11") (pin "1") (pinfunction "1_1") (pintype "passive"))
      (node (ref "R31") (pin "1") (pinfunction "1_1") (pintype "passive"))
      (node (ref "U2") (pin "3") (pinfunction "+IN_3") (pintype "input"))
    )
    (net (code "50") (name "Net-(U2B--IN)") (class "Default")
      (node (ref "C22") (pin "1") (pinfunction "1_1") (pintype "passive"))
      (node (ref "R32") (pin "1") (pinfunction "1_1") (pintype "passive"))
      (node (ref "R33") (pin "1") (pinfunction "1_1") (pintype "passive"))
      (node (ref "U2") (pin "6") (pinfunction "-IN_6") (pintype "input"))
      (node (ref "U2") (pin "7") (pinfunction "OUT_7") (pintype "output"))
    )
    (net (code "51") (name "Net-(U2C-+IN)") (class "Default")
      (node (ref "R20") (pin "1") (pinfunction "1_1") (pintype "passive"))
      (node (ref "U2") (pin "10") (pinfunction "+IN_10") (pintype "input"))
      (node (ref "U2") (pin "14") (pinfunction "OUT_14") (pintype "output"))
    )
    (net (code "52") (name "Net-(U2C--IN)") (class "Default")
      (node (ref "LED2") (pin "A") (pinfunction "A_A") (pintype "passive"))
      (node (ref "R27") (pin "2") (pinfunction "2_2") (pintype "passive"))
      (node (ref "U2") (pin "9") (pinfunction "-IN_9") (pintype "input"))
    )
    (net (code "53") (name "Net-(U2D--IN)") (class "Default")
      (node (ref "R20") (pin "2") (pinfunction "2_2") (pintype "passive"))
      (node (ref "R21") (pin "1") (pinfunction "1_1") (pintype "passive"))
      (node (ref "R22") (pin "1") (pinfunction "1_1") (pintype "passive"))
      (node (ref "U2") (pin "13") (pinfunction "-IN_13") (pintype "input"))
    )
    (net (code "54") (name "unconnected-(OUT1-NORM-PadN)") (class "Default")
      (node (ref "OUT1") (pin "N") (pinfunction "NORM_N") (pintype "bidirectional"))
    )
    (net (code "55") (name "unconnected-(OUT2-NORM-PadN)") (class "Default")
      (node (ref "OUT2") (pin "N") (pinfunction "NORM_N") (pintype "bidirectional"))
    )
  )
)
